# mic.net
KiCad netlist of a schematic drawn in Altium Designer
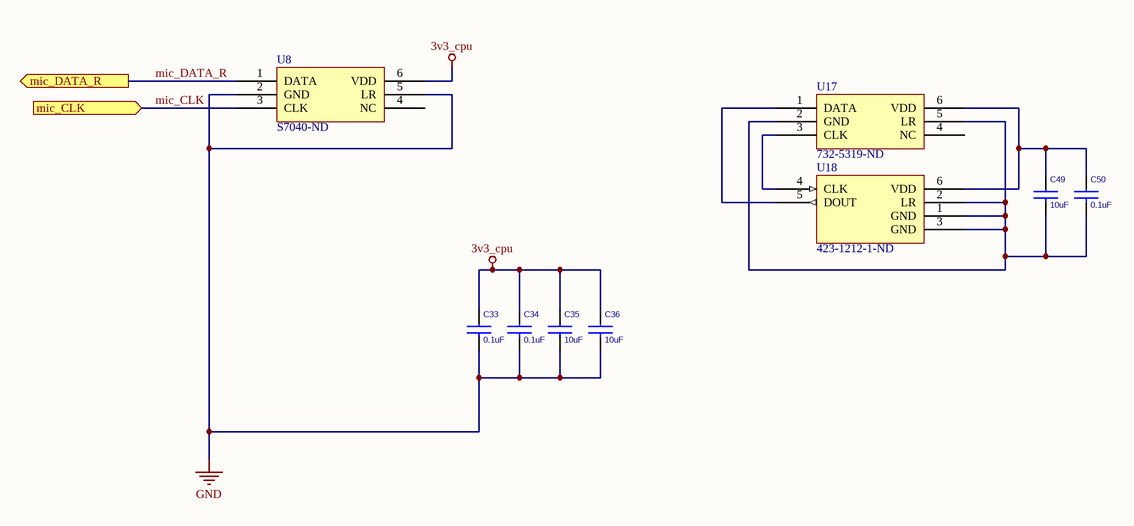
[diagram p0: mic.SchDoc]

(export (version "E")
  (design (tool "Eeschema 10.0.6"))
  (components
    (comp (ref "C33")
      (value "0.1uF")
      (footprint "CAPC2012X09M")
      (description "CAP CER 0.1UF 25V 10% X7R 0805")
      (libsource (lib "Capacitors") (part "CAP_SMD_0.1UF_10%"))
    )
    (comp (ref "C34")
      (value "0.1uF")
      (footprint "CAPC2012X09M")
      (description "CAP CER 0.1UF 25V 10% X7R 0805")
      (libsource (lib "Capacitors") (part "CAP_SMD_0.1UF_10%"))
    )
    (comp (ref "C35")
      (value "10uF")
      (footprint "CAPC2012X09M")
      (description "CAP CER 10UF 16V 20% X5R 0805")
      (libsource (lib "Capacitors") (part "CAP_SMD_10UF_20%"))
    )
    (comp (ref "C36")
      (value "10uF")
      (footprint "CAPC2012X09M")
      (description "CAP CER 10UF 16V 20% X5R 0805")
      (libsource (lib "Capacitors") (part "CAP_SMD_10UF_20%"))
    )
    (comp (ref "C49")
      (value "10uF")
      (footprint "CAPC2012X09M")
      (description "CAP CER 10UF 16V 20% X5R 0805")
      (libsource (lib "Capacitors") (part "CAP_SMD_10UF_20%"))
    )
    (comp (ref "C50")
      (value "0.1uF")
      (footprint "CAPC2012X09M")
      (description "CAP CER 0.1UF 25V 10% X7R 0805")
      (libsource (lib "Capacitors") (part "CAP_SMD_0.1UF_10%"))
    )
    (comp (ref "U8")
      (value "STEVAL-MKI129V1-MOUNT-MAMA")
      (footprint "STEVAL-MKI129V1")
      (fields (field (name "SUPPLIER PART NUMBER 1") "S7040-ND"))
      (libsource (lib "TruthEar") (part "STEVAL-MKI129V1-MOUNT-MAMA"))
    )
    (comp (ref "U17")
      (value "STEVAL-MKI129V1-MOUNT-PAPA")
      (footprint "STEVAL-MKI129V1")
      (fields (field (name "SUPPLIER PART NUMBER 1") "732-5319-ND"))
      (libsource (lib "TruthEar") (part "STEVAL-MKI129V1-MOUNT-PAPA"))
    )
    (comp (ref "U18")
      (value "SPM1437HM4H-B")
      (footprint "LGA6C165P2X3_376X472X125")
      (fields (field (name "SUPPLIER PART NUMBER 1") "423-1212-1-ND"))
      (libsource (lib "TruthEar") (part "SPM1437HM4H-B"))
    )
  )
  (nets
    (net (code "1") (name "/mic_CLK") (class "Default")
      (node (ref "U8") (pin "3") (pinfunction "CLK_3") (pintype "power_in"))
    )
    (net (code "2") (name "/mic_DATA_R") (class "Default")
      (node (ref "U8") (pin "1") (pinfunction "DATA_1") (pintype "power_in"))
    )
    (net (code "3") (name "3v3_cpu") (class "Default")
      (node (ref "C33") (pin "1") (pinfunction "1_1") (pintype "passive"))
      (node (ref "C34") (pin "1") (pinfunction "1_1") (pintype "passive"))
      (node (ref "C35") (pin "1") (pinfunction "1_1") (pintype "passive"))
      (node (ref "C36") (pin "1") (pinfunction "1_1") (pintype "passive"))
      (node (ref "U8") (pin "6") (pinfunction "VDD_6") (pintype "power_in"))
    )
    (net (code "4") (name "GND") (class "Default")
      (node (ref "C33") (pin "2") (pinfunction "2_2") (pintype "passive"))
      (node (ref "C34") (pin "2") (pinfunction "2_2") (pintype "passive"))
      (node (ref "C35") (pin "2") (pinfunction "2_2") (pintype "passive"))
      (node (ref "C36") (pin "2") (pinfunction "2_2") (pintype "passive"))
      (node (ref "U8") (pin "2") (pinfunction "GND_2") (pintype "power_in"))
      (node (ref "U8") (pin "5") (pinfunction "LR_5") (pintype "power_in"))
    )
    (net (code "5") (name "Net-(U17-CLK)") (class "Default")
      (node (ref "U17") (pin "3") (pinfunction "CLK_3") (pintype "power_in"))
      (node (ref "U18") (pin "4") (pinfunction "CLK_4") (pintype "input"))
    )
    (net (code "6") (name "Net-(U17-DATA)") (class "Default")
      (node (ref "U17") (pin "1") (pinfunction "DATA_1") (pintype "power_in"))
      (node (ref "U18") (pin "5") (pinfunction "DOUT_5") (pintype "output"))
    )
    (net (code "7") (name "Net-(U17-GND)") (class "Default")
      (node (ref "C49") (pin "2") (pinfunction "2_2") (pintype "passive"))
      (node (ref "C50") (pin "2") (pinfunction "2_2") (pintype "passive"))
      (node (ref "U17") (pin "2") (pinfunction "GND_2") (pintype "power_in"))
      (node (ref "U17") (pin "5") (pinfunction "LR_5") (pintype "power_in"))
      (node (ref "U18") (pin "1") (pinfunction "GND_1") (pintype "power_in"))
      (node (ref "U18") (pin "2") (pinfunction "LR_2") (pintype "power_in"))
      (node (ref "U18") (pin "3") (pinfunction "GND_3") (pintype "power_in"))
    )
    (net (code "8") (name "Net-(U17-VDD)") (class "Default")
      (node (ref "C49") (pin "1") (pinfunction "1_1") (pintype "passive"))
      (node (ref "C50") (pin "1") (pinfunction "1_1") (pintype "passive"))
      (node (ref "U17") (pin "6") (pinfunction "VDD_6") (pintype "power_in"))
      (node (ref "U18") (pin "6") (pinfunction "VDD_6") (pintype "power_in"))
    )
    (net (code "9") (name "unconnected-(U8-NC-Pad4)") (class "Default")
      (node (ref "U8") (pin "4") (pinfunction "NC_4") (pintype "power_in"))
    )
    (net (code "10") (name "unconnected-(U17-NC-Pad4)") (class "Default")
      (node (ref "U17") (pin "4") (pinfunction "NC_4") (pintype "power_in"))
    )
  )
)
